# W990D.net
KiCad netlist of a schematic drawn in EAGLE
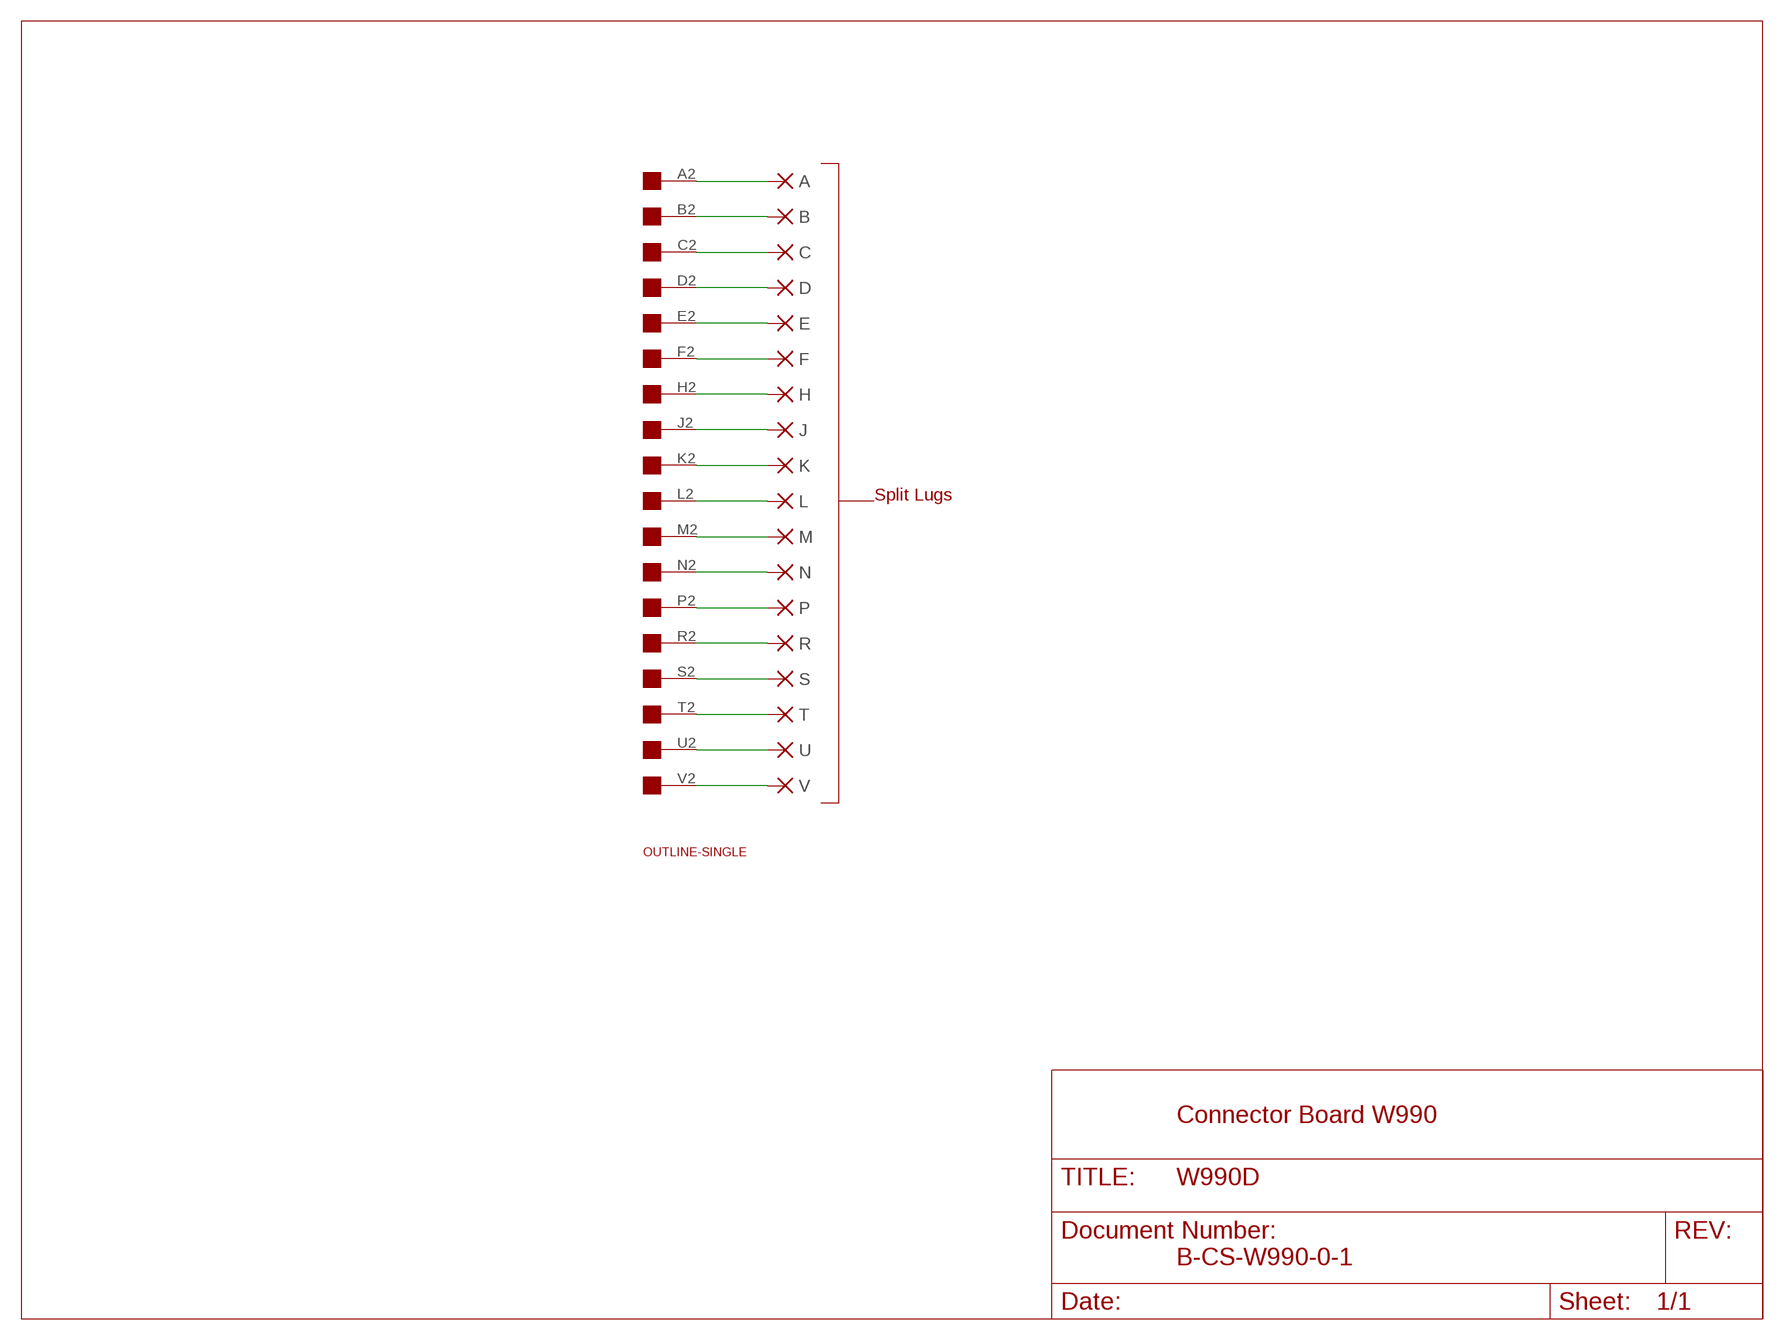
[diagram p0: schematic, sheet 1]

(export (version "E")
  (design (tool "Eeschema 10.0.6"))
  (components
    (comp (ref "A")
      (value "PAD-0465")
      (footprint "eagle-import:0465")
      (libsource (lib "eagle-import") (part "PAD-0465"))
    )
    (comp (ref "B")
      (value "PAD-0465")
      (footprint "eagle-import:0465")
      (libsource (lib "eagle-import") (part "PAD-0465"))
    )
    (comp (ref "C")
      (value "PAD-0465")
      (footprint "eagle-import:0465")
      (libsource (lib "eagle-import") (part "PAD-0465"))
    )
    (comp (ref "D")
      (value "PAD-0465")
      (footprint "eagle-import:0465")
      (libsource (lib "eagle-import") (part "PAD-0465"))
    )
    (comp (ref "E")
      (value "PAD-0465")
      (footprint "eagle-import:0465")
      (libsource (lib "eagle-import") (part "PAD-0465"))
    )
    (comp (ref "F")
      (value "PAD-0465")
      (footprint "eagle-import:0465")
      (libsource (lib "eagle-import") (part "PAD-0465"))
    )
    (comp (ref "H")
      (value "PAD-0465")
      (footprint "eagle-import:0465")
      (libsource (lib "eagle-import") (part "PAD-0465"))
    )
    (comp (ref "J")
      (value "PAD-0465")
      (footprint "eagle-import:0465")
      (libsource (lib "eagle-import") (part "PAD-0465"))
    )
    (comp (ref "K")
      (value "PAD-0465")
      (footprint "eagle-import:0465")
      (libsource (lib "eagle-import") (part "PAD-0465"))
    )
    (comp (ref "L")
      (value "PAD-0465")
      (footprint "eagle-import:0465")
      (libsource (lib "eagle-import") (part "PAD-0465"))
    )
    (comp (ref "M")
      (value "PAD-0465")
      (footprint "eagle-import:0465")
      (libsource (lib "eagle-import") (part "PAD-0465"))
    )
    (comp (ref "N")
      (value "PAD-0465")
      (footprint "eagle-import:0465")
      (libsource (lib "eagle-import") (part "PAD-0465"))
    )
    (comp (ref "P")
      (value "PAD-0465")
      (footprint "eagle-import:0465")
      (libsource (lib "eagle-import") (part "PAD-0465"))
    )
    (comp (ref "R")
      (value "PAD-0465")
      (footprint "eagle-import:0465")
      (libsource (lib "eagle-import") (part "PAD-0465"))
    )
    (comp (ref "S")
      (value "PAD-0465")
      (footprint "eagle-import:0465")
      (libsource (lib "eagle-import") (part "PAD-0465"))
    )
    (comp (ref "T")
      (value "PAD-0465")
      (footprint "eagle-import:0465")
      (libsource (lib "eagle-import") (part "PAD-0465"))
    )
    (comp (ref "U")
      (value "PAD-0465")
      (footprint "eagle-import:0465")
      (libsource (lib "eagle-import") (part "PAD-0465"))
    )
    (comp (ref "U$2")
      (value "OUTLINE-SINGLE")
      (footprint "eagle-import:SINGLE")
      (libsource (lib "eagle-import") (part "OUTLINE-SINGLE"))
    )
    (comp (ref "U$4")
      (value "EDGE-1")
      (footprint "eagle-import:EDGE-CON1")
      (libsource (lib "eagle-import") (part "EDGE-1"))
    )
    (comp (ref "V")
      (value "PAD-0465")
      (footprint "eagle-import:0465")
      (libsource (lib "eagle-import") (part "PAD-0465"))
    )
  )
  (nets
    (net (code "1") (name "Net-(A-P)") (class "Default")
      (node (ref "A") (pin "P$1") (pinfunction "P_P$1") (pintype "passive"))
      (node (ref "U$4") (pin "A2") (pinfunction "1_A2") (pintype "bidirectional"))
    )
    (net (code "2") (name "Net-(B-P)") (class "Default")
      (node (ref "B") (pin "P$1") (pinfunction "P_P$1") (pintype "passive"))
      (node (ref "U$4") (pin "B2") (pinfunction "1_B2") (pintype "bidirectional"))
    )
    (net (code "3") (name "Net-(C-P)") (class "Default")
      (node (ref "C") (pin "P$1") (pinfunction "P_P$1") (pintype "passive"))
      (node (ref "U$4") (pin "C2") (pinfunction "1_C2") (pintype "bidirectional"))
    )
    (net (code "4") (name "Net-(D-P)") (class "Default")
      (node (ref "D") (pin "P$1") (pinfunction "P_P$1") (pintype "passive"))
      (node (ref "U$4") (pin "D2") (pinfunction "1_D2") (pintype "bidirectional"))
    )
    (net (code "5") (name "Net-(E-P)") (class "Default")
      (node (ref "E") (pin "P$1") (pinfunction "P_P$1") (pintype "passive"))
      (node (ref "U$4") (pin "E2") (pinfunction "1_E2") (pintype "bidirectional"))
    )
    (net (code "6") (name "Net-(F-P)") (class "Default")
      (node (ref "F") (pin "P$1") (pinfunction "P_P$1") (pintype "passive"))
      (node (ref "U$4") (pin "F2") (pinfunction "1_F2") (pintype "bidirectional"))
    )
    (net (code "7") (name "Net-(H-P)") (class "Default")
      (node (ref "H") (pin "P$1") (pinfunction "P_P$1") (pintype "passive"))
      (node (ref "U$4") (pin "H2") (pinfunction "1_H2") (pintype "bidirectional"))
    )
    (net (code "8") (name "Net-(J-P)") (class "Default")
      (node (ref "J") (pin "P$1") (pinfunction "P_P$1") (pintype "passive"))
      (node (ref "U$4") (pin "J2") (pinfunction "1_J2") (pintype "bidirectional"))
    )
    (net (code "9") (name "Net-(K-P)") (class "Default")
      (node (ref "K") (pin "P$1") (pinfunction "P_P$1") (pintype "passive"))
      (node (ref "U$4") (pin "K2") (pinfunction "1_K2") (pintype "bidirectional"))
    )
    (net (code "10") (name "Net-(L-P)") (class "Default")
      (node (ref "L") (pin "P$1") (pinfunction "P_P$1") (pintype "passive"))
      (node (ref "U$4") (pin "L2") (pinfunction "1_L2") (pintype "bidirectional"))
    )
    (net (code "11") (name "Net-(M-P)") (class "Default")
      (node (ref "M") (pin "P$1") (pinfunction "P_P$1") (pintype "passive"))
      (node (ref "U$4") (pin "M2") (pinfunction "1_M2") (pintype "bidirectional"))
    )
    (net (code "12") (name "Net-(N-P)") (class "Default")
      (node (ref "N") (pin "P$1") (pinfunction "P_P$1") (pintype "passive"))
      (node (ref "U$4") (pin "N2") (pinfunction "1_N2") (pintype "bidirectional"))
    )
    (net (code "13") (name "Net-(P-P)") (class "Default")
      (node (ref "P") (pin "P$1") (pinfunction "P_P$1") (pintype "passive"))
      (node (ref "U$4") (pin "P2") (pinfunction "1_P2") (pintype "bidirectional"))
    )
    (net (code "14") (name "Net-(R-P)") (class "Default")
      (node (ref "R") (pin "P$1") (pinfunction "P_P$1") (pintype "passive"))
      (node (ref "U$4") (pin "R2") (pinfunction "1_R2") (pintype "bidirectional"))
    )
    (net (code "15") (name "Net-(S-P)") (class "Default")
      (node (ref "S") (pin "P$1") (pinfunction "P_P$1") (pintype "passive"))
      (node (ref "U$4") (pin "S2") (pinfunction "1_S2") (pintype "bidirectional"))
    )
    (net (code "16") (name "Net-(T-P)") (class "Default")
      (node (ref "T") (pin "P$1") (pinfunction "P_P$1") (pintype "passive"))
      (node (ref "U$4") (pin "T2") (pinfunction "1_T2") (pintype "bidirectional"))
    )
    (net (code "17") (name "Net-(U$4Q-1)") (class "Default")
      (node (ref "U") (pin "P$1") (pinfunction "P_P$1") (pintype "passive"))
      (node (ref "U$4") (pin "U2") (pinfunction "1_U2") (pintype "bidirectional"))
    )
    (net (code "18") (name "Net-(U$4R-1)") (class "Default")
      (node (ref "U$4") (pin "V2") (pinfunction "1_V2") (pintype "bidirectional"))
      (node (ref "V") (pin "P$1") (pinfunction "P_P$1") (pintype "passive"))
    )
  )
)
